# 3_MCU.net
KiCad netlist of a schematic drawn in Altium Designer
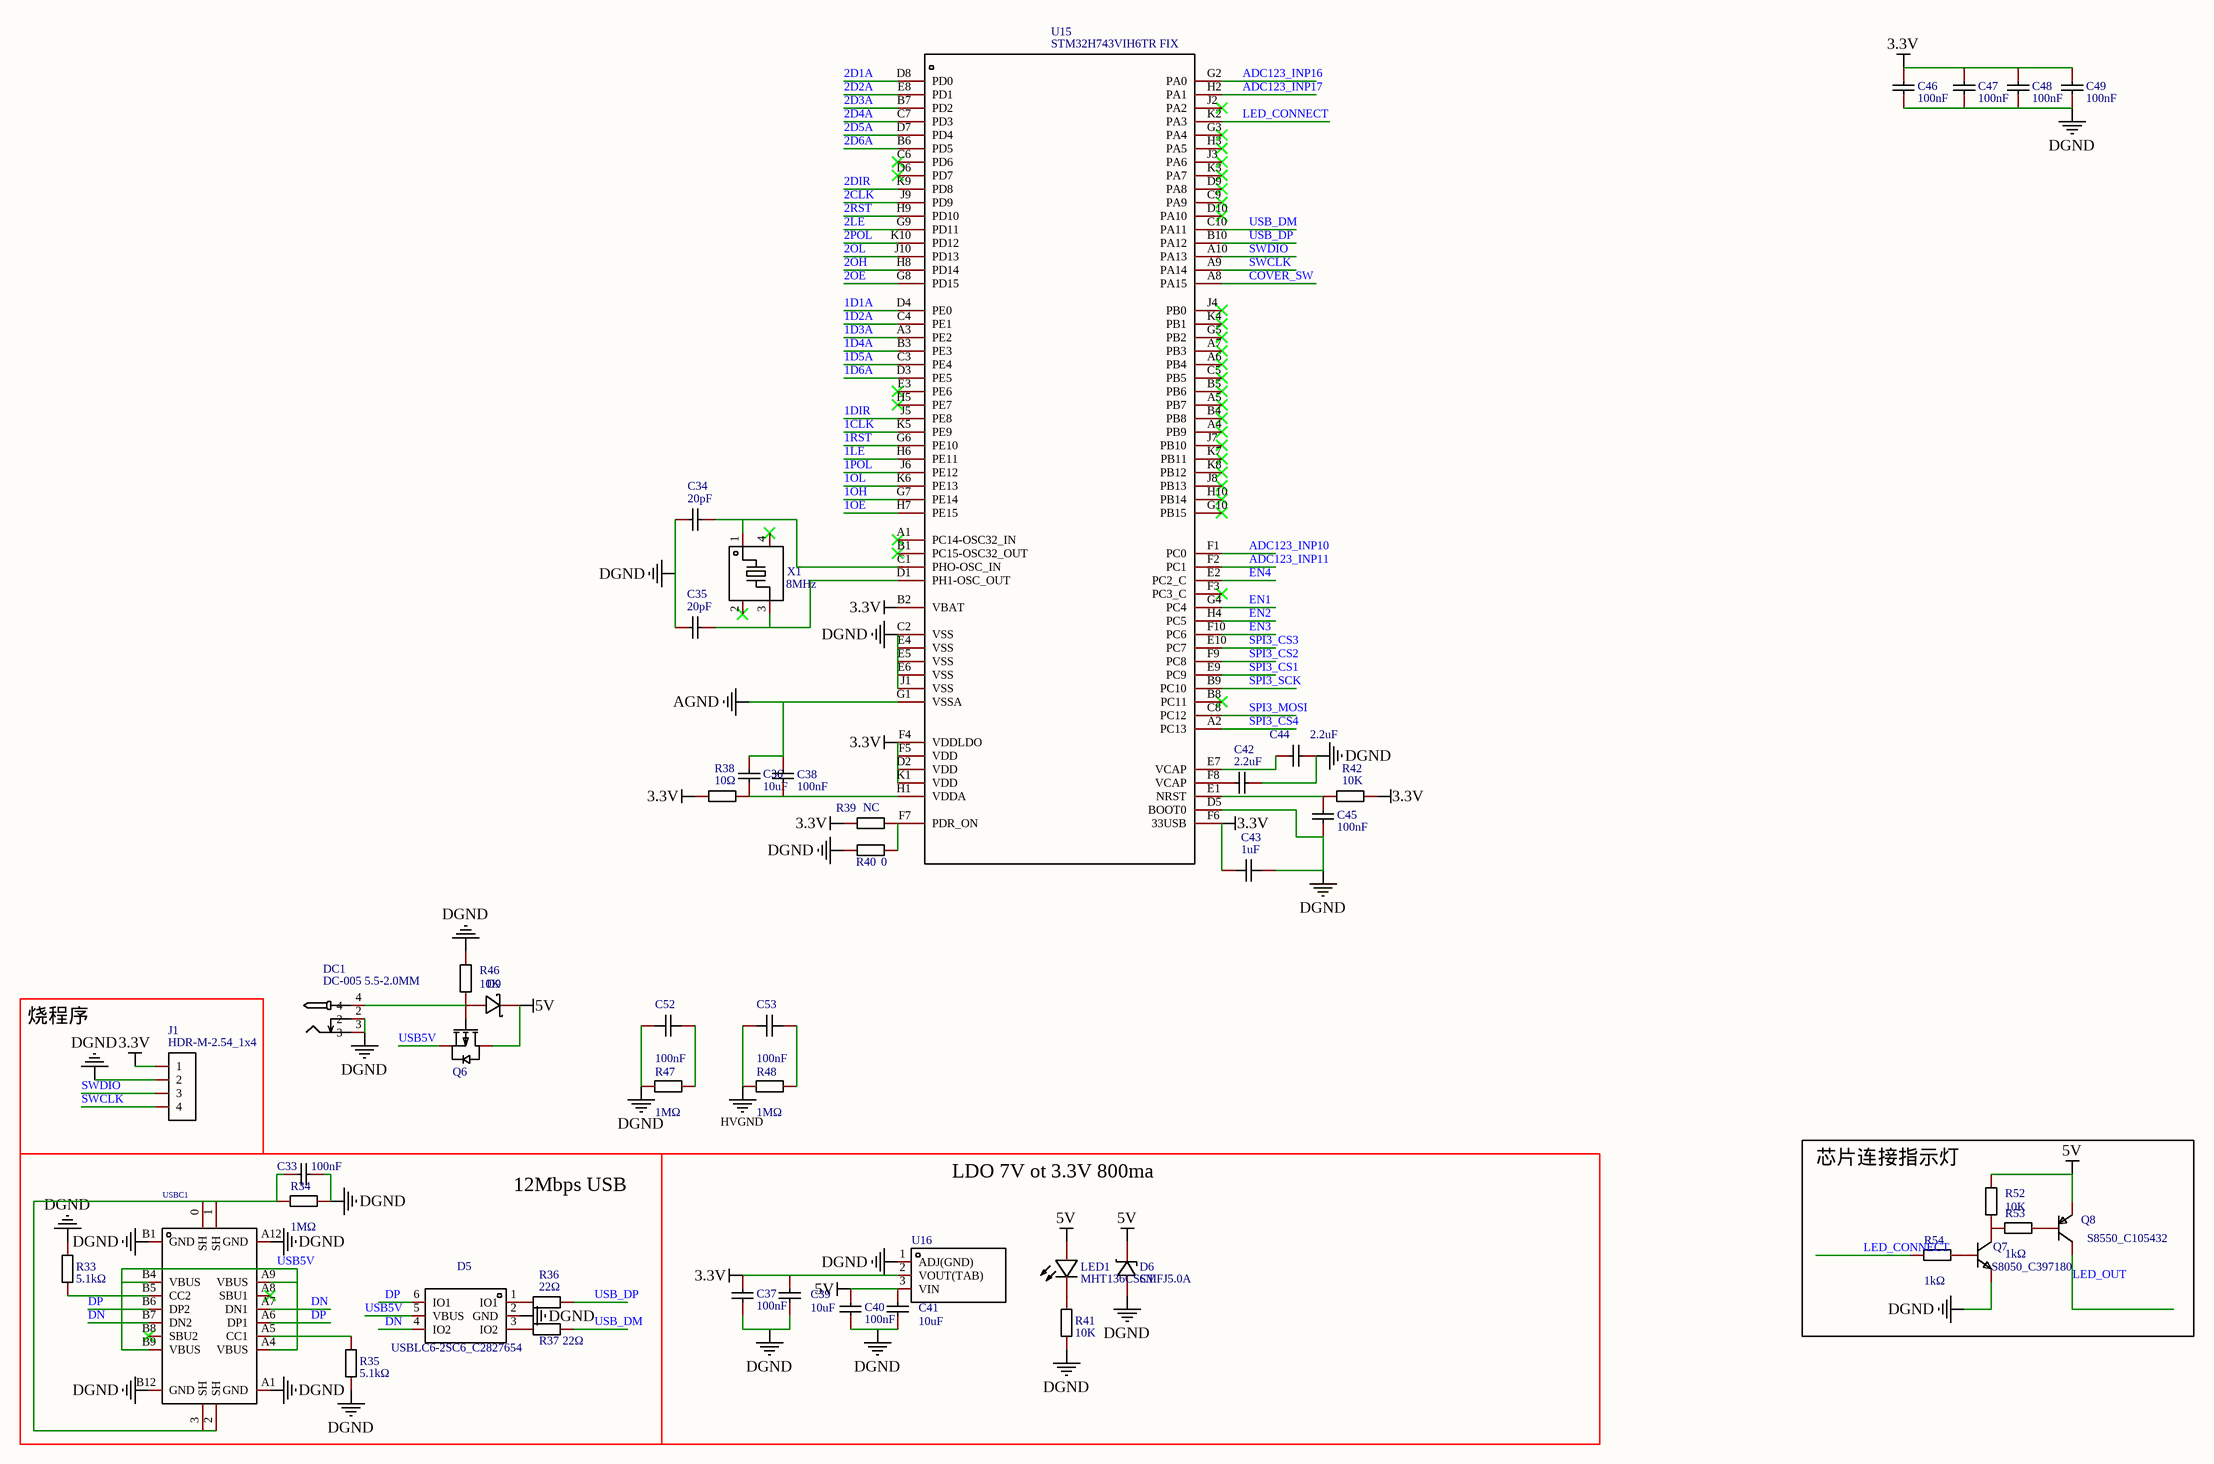
[diagram p0: 3_MCU.schdoc]

(export (version "E")
  (design (tool "Eeschema 10.0.6"))
  (components
    (comp (ref "C33")
      (value "100nF")
      (fields
        (field (name "NAME") "100nF")
        (field (name "MANUFACTURER PART") "CL05B104KO5NNNC")
        (field (name "MANUFACTURER") "SAMSUNG")
      )
      (libsource (lib "altium-import") (part "root_2_CL05B104KO5NNNC_"))
    )
    (comp (ref "C34")
      (value "20pF")
      (fields
        (field (name "NAME") "20pF")
        (field (name "MANUFACTURER") "FH")
        (field (name "MANUFACTURER PART") "0402CG200J500NT")
      )
      (libsource (lib "altium-import") (part "root_2_0402CG200J500NT_"))
    )
    (comp (ref "C35")
      (value "20pF")
      (fields
        (field (name "NAME") "20pF")
        (field (name "MANUFACTURER") "FH")
        (field (name "MANUFACTURER PART") "0402CG200J500NT")
      )
      (libsource (lib "altium-import") (part "root_2_0402CG200J500NT_"))
    )
    (comp (ref "C36")
      (value "10uF")
      (fields
        (field (name "NAME") "10uF")
        (field (name "MANUFACTURER PART") "CL05A106MQ5NUNC")
        (field (name "MANUFACTURER") "SAMSUNG")
      )
      (libsource (lib "altium-import") (part "root_1_CL05A106MQ5NUNC_"))
    )
    (comp (ref "C37")
      (value "100nF")
      (fields
        (field (name "NAME") "100nF")
        (field (name "MANUFACTURER PART") "CL05B104KO5NNNC")
        (field (name "MANUFACTURER") "SAMSUNG")
      )
      (libsource (lib "altium-import") (part "root_1_CL05B104KO5NNNC_"))
    )
    (comp (ref "C38")
      (value "100nF")
      (fields
        (field (name "NAME") "100nF")
        (field (name "MANUFACTURER PART") "CL05B104KO5NNNC")
        (field (name "MANUFACTURER") "SAMSUNG")
      )
      (libsource (lib "altium-import") (part "root_1_CL05B104KO5NNNC_"))
    )
    (comp (ref "C39")
      (value "10uF")
      (description "容值:10uF;精度:±20%;额定电压:6.3V;材质(温度系数):X5R;")
      (fields
        (field (name "MANUFACTURER") "SAMSUNG(三星)")
        (field (name "MANUFACTURER PART") "CL05A106MQ5NUNC")
      )
      (libsource (lib "altium-import") (part "root_1_CL05A106MQ5NUNC_"))
    )
    (comp (ref "C40")
      (value "100nF")
      (fields
        (field (name "NAME") "100nF")
        (field (name "MANUFACTURER PART") "CL05B104KO5NNNC")
        (field (name "MANUFACTURER") "SAMSUNG")
      )
      (libsource (lib "altium-import") (part "root_1_CL05B104KO5NNNC_"))
    )
    (comp (ref "C41")
      (value "10uF")
      (description "容值:10uF;精度:±20%;额定电压:6.3V;材质(温度系数):X5R;")
      (fields
        (field (name "MANUFACTURER") "SAMSUNG(三星)")
        (field (name "MANUFACTURER PART") "CL05A106MQ5NUNC")
      )
      (libsource (lib "altium-import") (part "root_1_CL05A106MQ5NUNC_"))
    )
    (comp (ref "C42")
      (value "2.2uF")
      (fields
        (field (name "NAME") "2.2uF")
        (field (name "MANUFACTURER PART") "GRM155R61A225KE95D")
        (field (name "MANUFACTURER") "MuRata")
      )
      (libsource (lib "altium-import") (part "root_0_GRM155R61A225KE95D_"))
    )
    (comp (ref "C43")
      (value "1uF")
      (fields
        (field (name "NAME") "1uF")
        (field (name "MANUFACTURER") "SAMSUNG")
        (field (name "MANUFACTURER PART") "CL05A105KA5NQNC")
      )
      (libsource (lib "altium-import") (part "root_2_CL05A105KA5NQNC_"))
    )
    (comp (ref "C44")
      (value "2.2uF")
      (fields
        (field (name "NAME") "2.2uF")
        (field (name "MANUFACTURER PART") "GRM155R61A225KE95D")
        (field (name "MANUFACTURER") "MuRata")
      )
      (libsource (lib "altium-import") (part "root_0_GRM155R61A225KE95D_"))
    )
    (comp (ref "C45")
      (value "100nF")
      (fields
        (field (name "NAME") "100nF")
        (field (name "MANUFACTURER PART") "CL05B104KO5NNNC")
        (field (name "MANUFACTURER") "SAMSUNG")
      )
      (libsource (lib "altium-import") (part "root_1_CL05B104KO5NNNC_"))
    )
    (comp (ref "C46")
      (value "100nF")
      (fields
        (field (name "NAME") "100nF")
        (field (name "MANUFACTURER PART") "CL05B104KO5NNNC")
        (field (name "MANUFACTURER") "SAMSUNG")
      )
      (libsource (lib "altium-import") (part "root_1_CL05B104KO5NNNC_"))
    )
    (comp (ref "C47")
      (value "100nF")
      (fields
        (field (name "NAME") "100nF")
        (field (name "MANUFACTURER PART") "CL05B104KO5NNNC")
        (field (name "MANUFACTURER") "SAMSUNG")
      )
      (libsource (lib "altium-import") (part "root_1_CL05B104KO5NNNC_"))
    )
    (comp (ref "C48")
      (value "100nF")
      (fields
        (field (name "NAME") "100nF")
        (field (name "MANUFACTURER PART") "CL05B104KO5NNNC")
        (field (name "MANUFACTURER") "SAMSUNG")
      )
      (libsource (lib "altium-import") (part "root_1_CL05B104KO5NNNC_"))
    )
    (comp (ref "C49")
      (value "100nF")
      (fields
        (field (name "NAME") "100nF")
        (field (name "MANUFACTURER PART") "CL05B104KO5NNNC")
        (field (name "MANUFACTURER") "SAMSUNG")
      )
      (libsource (lib "altium-import") (part "root_1_CL05B104KO5NNNC_"))
    )
    (comp (ref "C52")
      (value "100nF")
      (description "容值:100nF;精度:±10%;额定电压:50V;材质(温度系数):X7R;")
      (fields
        (field (name "MANUFACTURER") "YAGEO(国巨)")
        (field (name "MANUFACTURER PART") "CC0603KRX7R9BB104")
      )
      (libsource (lib "altium-import") (part "root_0_CC0603KRX7R9BB104_"))
    )
    (comp (ref "C53")
      (value "100nF")
      (description "容值:100nF;精度:±10%;额定电压:50V;材质(温度系数):X7R;")
      (fields
        (field (name "MANUFACTURER") "YAGEO(国巨)")
        (field (name "MANUFACTURER PART") "CC0603KRX7R9BB104")
      )
      (libsource (lib "altium-import") (part "root_0_CC0603KRX7R9BB104_"))
    )
    (comp (ref "D5")
      (value "USBLC6-2SC6_C2827654")
      (fields
        (field (name "NAME") "USBLC6-2SC6_C2827654")
        (field (name "MANUFACTURER") "TECH PUBLIC(台舟电子)")
        (field (name "MANUFACTURER PART") "USBLC6-2SC6")
      )
      (libsource (lib "altium-import") (part "root_2_USBLC6-2SC6_"))
    )
    (comp (ref "D6")
      (value "SMFJ5.0A")
      (fields (field (name "NAME") "SMFJ5.0A") (field (name "MANUFACTURER") "RUILON"))
      (libsource (lib "altium-import") (part "root_3_SMFJ5.0A_"))
    )
    (comp (ref "D9")
      (value "SS34_C8678")
      (description "二极管配置:独立式;直流反向耐压(Vr):40V;平均整流电流(Io):3A;正向压降(Vf):550mV@3A;")
      (fields (field (name "MANUFACTURER") "MDD") (field (name "MANUFACTURER PART") "SS34"))
      (libsource (lib "altium-import") (part "root_2_SS34_C8678_"))
    )
    (comp (ref "DC1")
      (value "DC-005 5.5-2.0MM")
      (fields (field (name "NAME") "DC-005 5.5-2.0MM") (field (name "MANUFACTURER") "BOOMELE"))
      (libsource (lib "altium-import") (part "root_0_DC-005 5.5-2.0MM_"))
    )
    (comp (ref "J1")
      (value "HDR-M-2.54_1x4")
      (fields (field (name "NAME") "HDR-M-2.54_1x4"))
      (libsource (lib "altium-import") (part "root_0_HDR-M-2.54_1x4_"))
    )
    (comp (ref "LED1")
      (value "MHT136CSCT")
      (fields (field (name "NAME") "MHT136CSCT") (field (name "MANUFACTURER") "MEIHUA"))
      (libsource (lib "altium-import") (part "root_1_MHT136CSCT_"))
    )
    (comp (ref "Q6")
      (value "CJ3401")
      (description "类型:P沟道;漏源电压(Vdss):30V;连续漏极电流(Id):4.2A;功率(Pd):350mW;导通电阻(RDS(on)@Vgs,Id):65mΩ@10V,4.2A;")
      (fields (field (name "MANUFACTURER") "CJ(江苏长电/长晶)"))
      (libsource (lib "altium-import") (part "root_3_CJ3401_"))
    )
    (comp (ref "Q7")
      (value "S8050_C397180")
      (fields
        (field (name "NAME") "S8050_C397180")
        (field (name "MANUFACTURER") "AnBon")
        (field (name "MANUFACTURER PART") "S8050")
      )
      (libsource (lib "altium-import") (part "root_0_S8050_C397180_"))
    )
    (comp (ref "Q8")
      (value "S8550_C105432")
      (fields
        (field (name "NAME") "S8550_C105432")
        (field (name "MANUFACTURER") "CJ")
        (field (name "MANUFACTURER PART") "S8550")
      )
      (libsource (lib "altium-import") (part "root_2_S8550_C105432_"))
    )
    (comp (ref "R33")
      (value "5.1kΩ")
      (fields
        (field (name "NAME") "5.1kΩ")
        (field (name "MANUFACTURER") "UniOhm")
        (field (name "MANUFACTURER PART") "0402WGF5101TCE")
      )
      (libsource (lib "altium-import") (part "root_1_0402WGF5101TCE_"))
    )
    (comp (ref "R34")
      (value "1MΩ")
      (description "电阻类型:厚膜电阻;阻值:1MΩ;精度:±1%;功率:62.5mW;")
      (fields
        (field (name "MANUFACTURER") "UNI-ROYAL(厚声)")
        (field (name "MANUFACTURER PART") "0402WGF1004TCE")
      )
      (libsource (lib "altium-import") (part "root_0_0402WGF1004TCE_"))
    )
    (comp (ref "R35")
      (value "5.1kΩ")
      (fields
        (field (name "NAME") "5.1kΩ")
        (field (name "MANUFACTURER") "UniOhm")
        (field (name "MANUFACTURER PART") "0402WGF5101TCE")
      )
      (libsource (lib "altium-import") (part "root_1_0402WGF5101TCE_"))
    )
    (comp (ref "R36")
      (value "22Ω")
      (fields
        (field (name "NAME") "22Ω")
        (field (name "MANUFACTURER") "UniOhm")
        (field (name "MANUFACTURER PART") "0402WGF220JTCE")
      )
      (libsource (lib "altium-import") (part "root_0_0402WGF220JTCE_"))
    )
    (comp (ref "R37")
      (value "22Ω")
      (fields
        (field (name "NAME") "22Ω")
        (field (name "MANUFACTURER") "UniOhm")
        (field (name "MANUFACTURER PART") "0402WGF220JTCE")
      )
      (libsource (lib "altium-import") (part "root_0_0402WGF220JTCE_"))
    )
    (comp (ref "R38")
      (value "10Ω")
      (fields
        (field (name "NAME") "10Ω")
        (field (name "MANUFACTURER") "UniOhm")
        (field (name "MANUFACTURER PART") "0402WGF100JTCE")
      )
      (libsource (lib "altium-import") (part "root_0_0402WGF100JTCE_"))
    )
    (comp (ref "R39")
      (value "NC")
      (fields (field (name "NAME") "NC") (field (name "MANUFACTURER") "UniOhm"))
      (libsource (lib "altium-import") (part "root_0_NC_"))
    )
    (comp (ref "R40")
      (value "0")
      (fields
        (field (name "NAME") "0")
        (field (name "MANUFACTURER") "UniOhm")
        (field (name "MANUFACTURER PART") "0402WGF100JTCE")
      )
      (libsource (lib "altium-import") (part "root_0_0402WGF100JTCE_"))
    )
    (comp (ref "R41")
      (value "10K")
      (fields
        (field (name "NAME") "10K")
        (field (name "MANUFACTURER") "UniOhm")
        (field (name "MANUFACTURER PART") "0402WGF1002TCE")
      )
      (libsource (lib "altium-import") (part "root_1_0402WGF1002TCE_"))
    )
    (comp (ref "R42")
      (value "10K")
      (fields
        (field (name "NAME") "10K")
        (field (name "MANUFACTURER") "UniOhm")
        (field (name "MANUFACTURER PART") "0402WGF1002TCE")
      )
      (libsource (lib "altium-import") (part "root_0_0402WGF1002TCE_"))
    )
    (comp (ref "R46")
      (value "10K")
      (fields
        (field (name "NAME") "10K")
        (field (name "MANUFACTURER") "UniOhm")
        (field (name "MANUFACTURER PART") "0402WGF1002TCE")
      )
      (libsource (lib "altium-import") (part "root_1_0402WGF1002TCE_"))
    )
    (comp (ref "R47")
      (value "1MΩ")
      (description "电阻类型:厚膜电阻;阻值:1MΩ;精度:±1%;功率:100mW;")
      (fields
        (field (name "MANUFACTURER") "UNI-ROYAL(厚声)")
        (field (name "MANUFACTURER PART") "0603WAF1004T5E")
      )
      (libsource (lib "altium-import") (part "root_0_0603WAF1004T5E_"))
    )
    (comp (ref "R48")
      (value "1MΩ")
      (description "电阻类型:厚膜电阻;阻值:1MΩ;精度:±1%;功率:100mW;")
      (fields
        (field (name "MANUFACTURER") "UNI-ROYAL(厚声)")
        (field (name "MANUFACTURER PART") "0603WAF1004T5E")
      )
      (libsource (lib "altium-import") (part "root_0_0603WAF1004T5E_"))
    )
    (comp (ref "R52")
      (value "10K")
      (fields
        (field (name "NAME") "10K")
        (field (name "MANUFACTURER") "UniOhm")
        (field (name "MANUFACTURER PART") "0402WGF1002TCE")
      )
      (libsource (lib "altium-import") (part "root_1_0402WGF1002TCE_"))
    )
    (comp (ref "R53")
      (value "1kΩ")
      (description "电阻类型:厚膜电阻;阻值:1kΩ;精度:±1%;功率:62.5mW;")
      (fields
        (field (name "MANUFACTURER") "UNI-ROYAL(厚声)")
        (field (name "MANUFACTURER PART") "0402WGF1001TCE")
      )
      (libsource (lib "altium-import") (part "root_0_0402WGF1001TCE_"))
    )
    (comp (ref "R54")
      (value "1kΩ")
      (description "电阻类型:厚膜电阻;阻值:1kΩ;精度:±1%;功率:62.5mW;")
      (fields
        (field (name "MANUFACTURER") "UNI-ROYAL(厚声)")
        (field (name "MANUFACTURER PART") "0402WGF1001TCE")
      )
      (libsource (lib "altium-import") (part "root_0_0402WGF1001TCE_"))
    )
    (comp (ref "U15")
      (value "STM32H743VIH6TR FIX")
      (fields
        (field (name "NAME") "STM32H743VIH6TR FIX")
        (field (name "MANUFACTURER") "ST(意法半导体)")
        (field (name "MANUFACTURER PART") "STM32H743VIH6TR")
      )
      (libsource (lib "altium-import") (part "root_0_STM32H743VIH6TR_"))
    )
    (comp (ref "U16")
      (value "AMS1117-3.3_C347256")
      (description "输出类型:固定;输出极性:正;最大输入电压:18V;输出电压:3.3V;输出电流:1A;电源纹波抑制比(PSRR):60dB@(120Hz);")
      (fields (field (name "MANUFACTURER") "UMW(广东友台半导体)") (field (name "MANUFACTURER PART") "AMS1117-3.3"))
      (libsource (lib "altium-import") (part "root_0_AMS1117-3.3_C347256_"))
    )
    (comp (ref "USBC1")
      (value "TYPE-C-31-M-12")
      (description "连接器类型:Type-C;标准:-;公母:母座;触点数量:16P;端口数量:1;安装方式:-;额定电流 - 电源:5A;触头材质:-;触头镀层:-;工作温度范围:-;焊接温度(最大值):-;")
      (fields (field (name "MANUFACTURER") "韩国韩荣"))
      (libsource (lib "altium-import") (part "root_0_TYPE-C-31-M-12_"))
    )
    (comp (ref "X1")
      (value "8MHz")
      (fields
        (field (name "NAME") "8MHz")
        (field (name "MANUFACTURER") "Suzhou Liming Elec")
        (field (name "MANUFACTURER PART") "3225-8.00-20-10-10/A")
      )
      (libsource (lib "altium-import") (part "root_3_3225-8.00-20-10-10/A_"))
    )
  )
  (nets
    (net (code "1") (name "/1CLK") (class "Default")
      (node (ref "U15") (pin "K5") (pinfunction "PE9_K5") (pintype "passive"))
    )
    (net (code "2") (name "/1D1A") (class "Default")
      (node (ref "U15") (pin "D4") (pinfunction "PE0_D4") (pintype "passive"))
    )
    (net (code "3") (name "/1D2A") (class "Default")
      (node (ref "U15") (pin "C4") (pinfunction "PE1_C4") (pintype "passive"))
    )
    (net (code "4") (name "/1D3A") (class "Default")
      (node (ref "U15") (pin "A3") (pinfunction "PE2_A3") (pintype "passive"))
    )
    (net (code "5") (name "/1D4A") (class "Default")
      (node (ref "U15") (pin "B3") (pinfunction "PE3_B3") (pintype "passive"))
    )
    (net (code "6") (name "/1D5A") (class "Default")
      (node (ref "U15") (pin "C3") (pinfunction "PE4_C3") (pintype "passive"))
    )
    (net (code "7") (name "/1D6A") (class "Default")
      (node (ref "U15") (pin "D3") (pinfunction "PE5_D3") (pintype "passive"))
    )
    (net (code "8") (name "/1DIR") (class "Default")
      (node (ref "U15") (pin "J5") (pinfunction "PE8_J5") (pintype "passive"))
    )
    (net (code "9") (name "/1LE") (class "Default")
      (node (ref "U15") (pin "H6") (pinfunction "PE11_H6") (pintype "passive"))
    )
    (net (code "10") (name "/1OE") (class "Default")
      (node (ref "U15") (pin "H7") (pinfunction "PE15_H7") (pintype "passive"))
    )
    (net (code "11") (name "/1OH") (class "Default")
      (node (ref "U15") (pin "G7") (pinfunction "PE14_G7") (pintype "passive"))
    )
    (net (code "12") (name "/1OL") (class "Default")
      (node (ref "U15") (pin "K6") (pinfunction "PE13_K6") (pintype "passive"))
    )
    (net (code "13") (name "/1POL") (class "Default")
      (node (ref "U15") (pin "J6") (pinfunction "PE12_J6") (pintype "passive"))
    )
    (net (code "14") (name "/1RST") (class "Default")
      (node (ref "U15") (pin "G6") (pinfunction "PE10_G6") (pintype "passive"))
    )
    (net (code "15") (name "/2CLK") (class "Default")
      (node (ref "U15") (pin "J9") (pinfunction "PD9_J9") (pintype "passive"))
    )
    (net (code "16") (name "/2D1A") (class "Default")
      (node (ref "U15") (pin "D8") (pinfunction "PD0_D8") (pintype "passive"))
    )
    (net (code "17") (name "/2D2A") (class "Default")
      (node (ref "U15") (pin "E8") (pinfunction "PD1_E8") (pintype "passive"))
    )
    (net (code "18") (name "/2D3A") (class "Default")
      (node (ref "U15") (pin "B7") (pinfunction "PD2_B7") (pintype "passive"))
    )
    (net (code "19") (name "/2D4A") (class "Default")
      (node (ref "U15") (pin "C7") (pinfunction "PD3_C7") (pintype "passive"))
    )
    (net (code "20") (name "/2D5A") (class "Default")
      (node (ref "U15") (pin "D7") (pinfunction "PD4_D7") (pintype "passive"))
    )
    (net (code "21") (name "/2D6A") (class "Default")
      (node (ref "U15") (pin "B6") (pinfunction "PD5_B6") (pintype "passive"))
    )
    (net (code "22") (name "/2DIR") (class "Default")
      (node (ref "U15") (pin "K9") (pinfunction "PD8_K9") (pintype "passive"))
    )
    (net (code "23") (name "/2LE") (class "Default")
      (node (ref "U15") (pin "G9") (pinfunction "PD11_G9") (pintype "passive"))
    )
    (net (code "24") (name "/2OE") (class "Default")
      (node (ref "U15") (pin "G8") (pinfunction "PD15_G8") (pintype "passive"))
    )
    (net (code "25") (name "/2OH") (class "Default")
      (node (ref "U15") (pin "H8") (pinfunction "PD14_H8") (pintype "passive"))
    )
    (net (code "26") (name "/2OL") (class "Default")
      (node (ref "U15") (pin "J10") (pinfunction "PD13_J10") (pintype "passive"))
    )
    (net (code "27") (name "/2POL") (class "Default")
      (node (ref "U15") (pin "K10") (pinfunction "PD12_K10") (pintype "passive"))
    )
    (net (code "28") (name "/2RST") (class "Default")
      (node (ref "U15") (pin "H9") (pinfunction "PD10_H9") (pintype "passive"))
    )
    (net (code "29") (name "/ADC123_INP10") (class "Default")
      (node (ref "U15") (pin "F1") (pinfunction "PC0_F1") (pintype "passive"))
    )
    (net (code "30") (name "/ADC123_INP11") (class "Default")
      (node (ref "U15") (pin "F2") (pinfunction "PC1_F2") (pintype "passive"))
    )
    (net (code "31") (name "/ADC123_INP16") (class "Default")
      (node (ref "U15") (pin "G2") (pinfunction "PA0_G2") (pintype "passive"))
    )
    (net (code "32") (name "/ADC123_INP17") (class "Default")
      (node (ref "U15") (pin "H2") (pinfunction "PA1_H2") (pintype "passive"))
    )
    (net (code "33") (name "/COVER_SW") (class "Default")
      (node (ref "U15") (pin "A8") (pinfunction "PA15_A8") (pintype "passive"))
    )
    (net (code "34") (name "/DN") (class "Default")
      (node (ref "D5") (pin "4") (pinfunction "IO2_4") (pintype "passive"))
      (node (ref "USBC1") (pin "A7") (pinfunction "DN1_A7") (pintype "passive"))
      (node (ref "USBC1") (pin "B7") (pinfunction "DN2_B7") (pintype "passive"))
    )
    (net (code "35") (name "/DP") (class "Default")
      (node (ref "D5") (pin "6") (pinfunction "IO1_6") (pintype "passive"))
      (node (ref "USBC1") (pin "A6") (pinfunction "DP1_A6") (pintype "passive"))
      (node (ref "USBC1") (pin "B6") (pinfunction "DP2_B6") (pintype "passive"))
    )
    (net (code "36") (name "/EN1") (class "Default")
      (node (ref "U15") (pin "G4") (pinfunction "PC4_G4") (pintype "passive"))
    )
    (net (code "37") (name "/EN2") (class "Default")
      (node (ref "U15") (pin "H4") (pinfunction "PC5_H4") (pintype "passive"))
    )
    (net (code "38") (name "/EN3") (class "Default")
      (node (ref "U15") (pin "F10") (pinfunction "PC6_F10") (pintype "passive"))
    )
    (net (code "39") (name "/EN4") (class "Default")
      (node (ref "U15") (pin "E2") (pinfunction "PC2_C_E2") (pintype "passive"))
    )
    (net (code "40") (name "/LED_CONNECT") (class "Default")
      (node (ref "R54") (pin "1") (pinfunction "1_1") (pintype "passive"))
      (node (ref "U15") (pin "K2") (pinfunction "PA3_K2") (pintype "passive"))
    )
    (net (code "41") (name "/LED_OUT") (class "Default")
      (node (ref "Q8") (pin "3") (pinfunction "3_3") (pintype "passive"))
    )
    (net (code "42") (name "/SPI3_CS1") (class "Default")
      (node (ref "U15") (pin "E9") (pinfunction "PC9_E9") (pintype "passive"))
    )
    (net (code "43") (name "/SPI3_CS2") (class "Default")
      (node (ref "U15") (pin "F9") (pinfunction "PC8_F9") (pintype "passive"))
    )
    (net (code "44") (name "/SPI3_CS3") (class "Default")
      (node (ref "U15") (pin "E10") (pinfunction "PC7_E10") (pintype "passive"))
    )
    (net (code "45") (name "/SPI3_CS4") (class "Default")
      (node (ref "U15") (pin "A2") (pinfunction "PC13_A2") (pintype "passive"))
    )
    (net (code "46") (name "/SPI3_MOSI") (class "Default")
      (node (ref "U15") (pin "C8") (pinfunction "PC12_C8") (pintype "passive"))
    )
    (net (code "47") (name "/SPI3_SCK") (class "Default")
      (node (ref "U15") (pin "B9") (pinfunction "PC10_B9") (pintype "passive"))
    )
    (net (code "48") (name "/SWCLK") (class "Default")
      (node (ref "J1") (pin "4") (pinfunction "4_4") (pintype "passive"))
      (node (ref "U15") (pin "A9") (pinfunction "PA14_A9") (pintype "passive"))
    )
    (net (code "49") (name "/SWDIO") (class "Default")
      (node (ref "J1") (pin "3") (pinfunction "3_3") (pintype "passive"))
      (node (ref "U15") (pin "A10") (pinfunction "PA13_A10") (pintype "passive"))
    )
    (net (code "50") (name "/USB5V") (class "Default")
      (node (ref "D5") (pin "5") (pinfunction "VBUS_5") (pintype "passive"))
      (node (ref "Q6") (pin "2") (pinfunction "S_2") (pintype "passive"))
      (node (ref "USBC1") (pin "A4") (pinfunction "VBUS_A4") (pintype "passive"))
      (node (ref "USBC1") (pin "A9") (pinfunction "VBUS_A9") (pintype "passive"))
      (node (ref "USBC1") (pin "B4") (pinfunction "VBUS_B4") (pintype "passive"))
      (node (ref "USBC1") (pin "B9") (pinfunction "VBUS_B9") (pintype "passive"))
    )
    (net (code "51") (name "/USB_DM") (class "Default")
      (node (ref "R37") (pin "2") (pinfunction "2_2") (pintype "passive"))
      (node (ref "U15") (pin "C10") (pinfunction "PA11_C10") (pintype "passive"))
    )
    (net (code "52") (name "/USB_DP") (class "Default")
      (node (ref "R36") (pin "2") (pinfunction "2_2") (pintype "passive"))
      (node (ref "U15") (pin "B10") (pinfunction "PA12_B10") (pintype "passive"))
    )
    (net (code "53") (name "3.3V") (class "Default")
      (node (ref "C37") (pin "2") (pinfunction "2_2") (pintype "passive"))
      (node (ref "C39") (pin "2") (pinfunction "2_2") (pintype "passive"))
      (node (ref "C43") (pin "2") (pinfunction "2_2") (pintype "passive"))
      (node (ref "C46") (pin "2") (pinfunction "2_2") (pintype "passive"))
      (node (ref "C47") (pin "2") (pinfunction "2_2") (pintype "passive"))
      (node (ref "C48") (pin "2") (pinfunction "2_2") (pintype "passive"))
      (node (ref "C49") (pin "2") (pinfunction "2_2") (pintype "passive"))
      (node (ref "J1") (pin "1") (pinfunction "1_1") (pintype "passive"))
      (node (ref "R38") (pin "1") (pinfunction "1_1") (pintype "passive"))
      (node (ref "R39") (pin "1") (pinfunction "1_1") (pintype "passive"))
      (node (ref "R42") (pin "2") (pinfunction "2_2") (pintype "passive"))
      (node (ref "U15") (pin "B2") (pinfunction "VBAT_B2") (pintype "passive"))
      (node (ref "U15") (pin "D2") (pinfunction "VDD_D2") (pintype "passive"))
      (node (ref "U15") (pin "F4") (pinfunction "VDDLDO_F4") (pintype "passive"))
      (node (ref "U15") (pin "F5") (pinfunction "VDD_F5") (pintype "passive"))
      (node (ref "U15") (pin "F6") (pinfunction "33USB_F6") (pintype "passive"))
      (node (ref "U15") (pin "K1") (pinfunction "VDD_K1") (pintype "passive"))
      (node (ref "U16") (pin "2") (pinfunction "VOUT(TAB)_2") (pintype "passive"))
    )
    (net (code "54") (name "5V") (class "Default")
      (node (ref "C40") (pin "2") (pinfunction "2_2") (pintype "passive"))
      (node (ref "C41") (pin "2") (pinfunction "2_2") (pintype "passive"))
      (node (ref "D6") (pin "1") (pinfunction "K_1") (pintype "passive"))
      (node (ref "D9") (pin "1") (pinfunction "K_1") (pintype "passive"))
      (node (ref "LED1") (pin "2") (pinfunction "A_2") (pintype "passive"))
      (node (ref "Q6") (pin "3") (pinfunction "D_3") (pintype "passive"))
      (node (ref "Q8") (pin "2") (pinfunction "2_2") (pintype "passive"))
      (node (ref "R52") (pin "2") (pinfunction "2_2") (pintype "passive"))
      (node (ref "U16") (pin "3") (pinfunction "VIN_3") (pintype "passive"))
    )
    (net (code "55") (name "AGND") (class "Default")
      (node (ref "C36") (pin "2") (pinfunction "2_2") (pintype "passive"))
      (node (ref "C38") (pin "2") (pinfunction "2_2") (pintype "passive"))
      (node (ref "U15") (pin "G1") (pinfunction "VSSA_G1") (pintype "passive"))
    )
    (net (code "56") (name "DGND") (class "Default")
      (node (ref "C33") (pin "1") (pinfunction "1_1") (pintype "passive"))
      (node (ref "C34") (pin "2") (pinfunction "2_2") (pintype "passive"))
      (node (ref "C35") (pin "2") (pinfunction "2_2") (pintype "passive"))
      (node (ref "C37") (pin "1") (pinfunction "1_1") (pintype "passive"))
      (node (ref "C39") (pin "1") (pinfunction "1_1") (pintype "passive"))
      (node (ref "C40") (pin "1") (pinfunction "1_1") (pintype "passive"))
      (node (ref "C41") (pin "1") (pinfunction "1_1") (pintype "passive"))
      (node (ref "C42") (pin "2") (pinfunction "2_2") (pintype "passive"))
      (node (ref "C43") (pin "1") (pinfunction "1_1") (pintype "passive"))
      (node (ref "C44") (pin "2") (pinfunction "2_2") (pintype "passive"))
      (node (ref "C45") (pin "1") (pinfunction "1_1") (pintype "passive"))
      (node (ref "C46") (pin "1") (pinfunction "1_1") (pintype "passive"))
      (node (ref "C47") (pin "1") (pinfunction "1_1") (pintype "passive"))
      (node (ref "C48") (pin "1") (pinfunction "1_1") (pintype "passive"))
      (node (ref "C49") (pin "1") (pinfunction "1_1") (pintype "passive"))
      (node (ref "C52") (pin "1") (pinfunction "1_1") (pintype "passive"))
      (node (ref "D5") (pin "2") (pinfunction "GND_2") (pintype "passive"))
      (node (ref "D6") (pin "2") (pinfunction "A_2") (pintype "passive"))
      (node (ref "DC1") (pin "2") (pinfunction "2_2") (pintype "passive"))
      (node (ref "DC1") (pin "3") (pinfunction "3_3") (pintype "passive"))
      (node (ref "J1") (pin "2") (pinfunction "2_2") (pintype "passive"))
      (node (ref "Q7") (pin "2") (pinfunction "E_2") (pintype "passive"))
      (node (ref "R33") (pin "2") (pinfunction "2_2") (pintype "passive"))
      (node (ref "R34") (pin "2") (pinfunction "2_2") (pintype "passive"))
      (node (ref "R35") (pin "1") (pinfunction "1_1") (pintype "passive"))
      (node (ref "R40") (pin "1") (pinfunction "1_1") (pintype "passive"))
      (node (ref "R41") (pin "1") (pinfunction "1_1") (pintype "passive"))
      (node (ref "R46") (pin "2") (pinfunction "2_2") (pintype "passive"))
      (node (ref "R47") (pin "1") (pinfunction "1_1") (pintype "passive"))
      (node (ref "U15") (pin "C2") (pinfunction "VSS_C2") (pintype "passive"))
      (node (ref "U15") (pin "D5") (pinfunction "BOOT0_D5") (pintype "passive"))
      (node (ref "U15") (pin "E4") (pinfunction "VSS_E4") (pintype "passive"))
      (node (ref "U15") (pin "E5") (pinfunction "VSS_E5") (pintype "passive"))
      (node (ref "U15") (pin "E6") (pinfunction "VSS_E6") (pintype "passive"))
      (node (ref "U15") (pin "J1") (pinfunction "VSS_J1") (pintype "passive"))
      (node (ref "U16") (pin "1") (pinfunction "ADJ(GND)_1") (pintype "passive"))
      (node (ref "USBC1") (pin "A1") (pinfunction "GND_A1") (pintype "passive"))
      (node (ref "USBC1") (pin "A12") (pinfunction "GND_A12") (pintype "passive"))
      (node (ref "USBC1") (pin "B1") (pinfunction "GND_B1") (pintype "passive"))
      (node (ref "USBC1") (pin "B12") (pinfunction "GND_B12") (pintype "passive"))
    )
    (net (code "57") (name "HVGND") (class "Default")
      (node (ref "C53") (pin "1") (pinfunction "1_1") (pintype "passive"))
      (node (ref "R48") (pin "1") (pinfunction "1_1") (pintype "passive"))
    )
    (net (code "58") (name "Net-(C33-Pad2)") (class "Default")
      (node (ref "C33") (pin "2") (pinfunction "2_2") (pintype "passive"))
      (node (ref "R34") (pin "1") (pinfunction "1_1") (pintype "passive"))
      (node (ref "USBC1") (pin "0") (pinfunction "SH_0") (pintype "passive"))
      (node (ref "USBC1") (pin "1") (pinfunction "SH_1") (pintype "passive"))
      (node (ref "USBC1") (pin "2") (pinfunction "SH_2") (pintype "passive"))
      (node (ref "USBC1") (pin "3") (pinfunction "SH_3") (pintype "passive"))
    )
    (net (code "59") (name "Net-(C42-Pad1)") (class "Default")
      (node (ref "C42") (pin "1") (pinfunction "1_1") (pintype "passive"))
      (node (ref "U15") (pin "F8") (pinfunction "VCAP_F8") (pintype "passive"))
    )
    (net (code "60") (name "Net-(C44-Pad1)") (class "Default")
      (node (ref "C44") (pin "1") (pinfunction "1_1") (pintype "passive"))
      (node (ref "U15") (pin "E7") (pinfunction "VCAP_E7") (pintype "passive"))
    )
    (net (code "61") (name "Net-(C52-Pad2)") (class "Default")
      (node (ref "C52") (pin "2") (pinfunction "2_2") (pintype "passive"))
      (node (ref "R47") (pin "2") (pinfunction "2_2") (pintype "passive"))
    )
    (net (code "62") (name "Net-(C53-Pad2)") (class "Default")
      (node (ref "C53") (pin "2") (pinfunction "2_2") (pintype "passive"))
      (node (ref "R48") (pin "2") (pinfunction "2_2") (pintype "passive"))
    )
    (net (code "63") (name "Net-(D5-IO1-Pad1)") (class "Default")
      (node (ref "D5") (pin "1") (pinfunction "IO1_1") (pintype "passive"))
      (node (ref "R36") (pin "1") (pinfunction "1_1") (pintype "passive"))
    )
    (net (code "64") (name "Net-(D5-IO2-Pad3)") (class "Default")
      (node (ref "D5") (pin "3") (pinfunction "IO2_3") (pintype "passive"))
      (node (ref "R37") (pin "1") (pinfunction "1_1") (pintype "passive"))
    )
    (net (code "65") (name "Net-(D9-A)") (class "Default")
      (node (ref "D9") (pin "2") (pinfunction "A_2") (pintype "passive"))
      (node (ref "DC1") (pin "4") (pinfunction "4_4") (pintype "passive"))
      (node (ref "Q6") (pin "1") (pinfunction "G_1") (pintype "passive"))
      (node (ref "R46") (pin "1") (pinfunction "1_1") (pintype "passive"))
    )
    (net (code "66") (name "Net-(LED1-K)") (class "Default")
      (node (ref "LED1") (pin "1") (pinfunction "K_1") (pintype "passive"))
      (node (ref "R41") (pin "2") (pinfunction "2_2") (pintype "passive"))
    )
    (net (code "67") (name "Net-(Q7-B)") (class "Default")
      (node (ref "Q7") (pin "1") (pinfunction "B_1") (pintype "passive"))
      (node (ref "R54") (pin "2") (pinfunction "2_2") (pintype "passive"))
    )
    (net (code "68") (name "Net-(Q7-C)") (class "Default")
      (node (ref "Q7") (pin "3") (pinfunction "C_3") (pintype "passive"))
      (node (ref "R52") (pin "1") (pinfunction "1_1") (pintype "passive"))
      (node (ref "R53") (pin "1") (pinfunction "1_1") (pintype "passive"))
    )
    (net (code "69") (name "Net-(Q8-Pad1)") (class "Default")
      (node (ref "Q8") (pin "1") (pinfunction "1_1") (pintype "passive"))
      (node (ref "R53") (pin "2") (pinfunction "2_2") (pintype "passive"))
    )
    (net (code "70") (name "Net-(U15-NRST)") (class "Default")
      (node (ref "C45") (pin "2") (pinfunction "2_2") (pintype "passive"))
      (node (ref "R42") (pin "1") (pinfunction "1_1") (pintype "passive"))
      (node (ref "U15") (pin "E1") (pinfunction "NRST_E1") (pintype "passive"))
    )
    (net (code "71") (name "Net-(U15-PDR_ON)") (class "Default")
      (node (ref "R39") (pin "2") (pinfunction "2_2") (pintype "passive"))
      (node (ref "R40") (pin "2") (pinfunction "2_2") (pintype "passive"))
      (node (ref "U15") (pin "F7") (pinfunction "PDR_ON_F7") (pintype "passive"))
    )
    (net (code "72") (name "Net-(U15-PH1-OSC_OUT)") (class "Default")
      (node (ref "C35") (pin "1") (pinfunction "1_1") (pintype "passive"))
      (node (ref "U15") (pin "D1") (pinfunction "PH1-OSC_OUT_D1") (pintype "passive"))
      (node (ref "X1") (pin "3") (pinfunction "3_3") (pintype "passive"))
    )
    (net (code "73") (name "Net-(U15-PHO-OSC_IN)") (class "Default")
      (node (ref "C34") (pin "1") (pinfunction "1_1") (pintype "passive"))
      (node (ref "U15") (pin "C1") (pinfunction "PHO-OSC_IN_C1") (pintype "passive"))
      (node (ref "X1") (pin "1") (pinfunction "1_1") (pintype "passive"))
    )
    (net (code "74") (name "Net-(U15-VDDA)") (class "Default")
      (node (ref "C36") (pin "1") (pinfunction "1_1") (pintype "passive"))
      (node (ref "C38") (pin "1") (pinfunction "1_1") (pintype "passive"))
      (node (ref "R38") (pin "2") (pinfunction "2_2") (pintype "passive"))
      (node (ref "U15") (pin "H1") (pinfunction "VDDA_H1") (pintype "passive"))
    )
    (net (code "75") (name "Net-(USBC1-CC1)") (class "Default")
      (node (ref "R35") (pin "2") (pinfunction "2_2") (pintype "passive"))
      (node (ref "USBC1") (pin "A5") (pinfunction "CC1_A5") (pintype "passive"))
    )
    (net (code "76") (name "Net-(USBC1-CC2)") (class "Default")
      (node (ref "R33") (pin "1") (pinfunction "1_1") (pintype "passive"))
      (node (ref "USBC1") (pin "B5") (pinfunction "CC2_B5") (pintype "passive"))
    )
    (net (code "77") (name "unconnected-(U15-PA2-PadJ2)") (class "Default")
      (node (ref "U15") (pin "J2") (pinfunction "PA2_J2") (pintype "passive+no_connect"))
    )
    (net (code "78") (name "unconnected-(U15-PA4-PadG3)") (class "Default")
      (node (ref "U15") (pin "G3") (pinfunction "PA4_G3") (pintype "passive+no_connect"))
    )
    (net (code "79") (name "unconnected-(U15-PA5-PadH3)") (class "Default")
      (node (ref "U15") (pin "H3") (pinfunction "PA5_H3") (pintype "passive+no_connect"))
    )
    (net (code "80") (name "unconnected-(U15-PA6-PadJ3)") (class "Default")
      (node (ref "U15") (pin "J3") (pinfunction "PA6_J3") (pintype "passive+no_connect"))
    )
    (net (code "81") (name "unconnected-(U15-PA7-PadK3)") (class "Default")
      (node (ref "U15") (pin "K3") (pinfunction "PA7_K3") (pintype "passive+no_connect"))
    )
    (net (code "82") (name "unconnected-(U15-PA8-PadD9)") (class "Default")
      (node (ref "U15") (pin "D9") (pinfunction "PA8_D9") (pintype "passive+no_connect"))
    )
    (net (code "83") (name "unconnected-(U15-PA9-PadC9)") (class "Default")
      (node (ref "U15") (pin "C9") (pinfunction "PA9_C9") (pintype "passive+no_connect"))
    )
    (net (code "84") (name "unconnected-(U15-PA10-PadD10)") (class "Default")
      (node (ref "U15") (pin "D10") (pinfunction "PA10_D10") (pintype "passive+no_connect"))
    )
    (net (code "85") (name "unconnected-(U15-PB0-PadJ4)") (class "Default")
      (node (ref "U15") (pin "J4") (pinfunction "PB0_J4") (pintype "passive+no_connect"))
    )
    (net (code "86") (name "unconnected-(U15-PB1-PadK4)") (class "Default")
      (node (ref "U15") (pin "K4") (pinfunction "PB1_K4") (pintype "passive+no_connect"))
    )
    (net (code "87") (name "unconnected-(U15-PB2-PadG5)") (class "Default")
      (node (ref "U15") (pin "G5") (pinfunction "PB2_G5") (pintype "passive+no_connect"))
    )
    (net (code "88") (name "unconnected-(U15-PB3-PadA7)") (class "Default")
      (node (ref "U15") (pin "A7") (pinfunction "PB3_A7") (pintype "passive+no_connect"))
    )
    (net (code "89") (name "unconnected-(U15-PB4-PadA6)") (class "Default")
      (node (ref "U15") (pin "A6") (pinfunction "PB4_A6") (pintype "passive+no_connect"))
    )
    (net (code "90") (name "unconnected-(U15-PB5-PadC5)") (class "Default")
      (node (ref "U15") (pin "C5") (pinfunction "PB5_C5") (pintype "passive+no_connect"))
    )
    (net (code "91") (name "unconnected-(U15-PB6-PadB5)") (class "Default")
      (node (ref "U15") (pin "B5") (pinfunction "PB6_B5") (pintype "passive+no_connect"))
    )
    (net (code "92") (name "unconnected-(U15-PB7-PadA5)") (class "Default")
      (node (ref "U15") (pin "A5") (pinfunction "PB7_A5") (pintype "passive+no_connect"))
    )
    (net (code "93") (name "unconnected-(U15-PB8-PadB4)") (class "Default")
      (node (ref "U15") (pin "B4") (pinfunction "PB8_B4") (pintype "passive+no_connect"))
    )
    (net (code "94") (name "unconnected-(U15-PB9-PadA4)") (class "Default")
      (node (ref "U15") (pin "A4") (pinfunction "PB9_A4") (pintype "passive+no_connect"))
    )
    (net (code "95") (name "unconnected-(U15-PB10-PadJ7)") (class "Default")
      (node (ref "U15") (pin "J7") (pinfunction "PB10_J7") (pintype "passive+no_connect"))
    )
    (net (code "96") (name "unconnected-(U15-PB11-PadK7)") (class "Default")
      (node (ref "U15") (pin "K7") (pinfunction "PB11_K7") (pintype "passive+no_connect"))
    )
    (net (code "97") (name "unconnected-(U15-PB12-PadK8)") (class "Default")
      (node (ref "U15") (pin "K8") (pinfunction "PB12_K8") (pintype "passive+no_connect"))
    )
    (net (code "98") (name "unconnected-(U15-PB13-PadJ8)") (class "Default")
      (node (ref "U15") (pin "J8") (pinfunction "PB13_J8") (pintype "passive+no_connect"))
    )
    (net (code "99") (name "unconnected-(U15-PB14-PadH10)") (class "Default")
      (node (ref "U15") (pin "H10") (pinfunction "PB14_H10") (pintype "passive+no_connect"))
    )
    (net (code "100") (name "unconnected-(U15-PB15-PadG10)") (class "Default")
      (node (ref "U15") (pin "G10") (pinfunction "PB15_G10") (pintype "passive+no_connect"))
    )
    (net (code "101") (name "unconnected-(U15-PC3_C-PadF3)") (class "Default")
      (node (ref "U15") (pin "F3") (pinfunction "PC3_C_F3") (pintype "passive+no_connect"))
    )
    (net (code "102") (name "unconnected-(U15-PC11-PadB8)") (class "Default")
      (node (ref "U15") (pin "B8") (pinfunction "PC11_B8") (pintype "passive+no_connect"))
    )
    (net (code "103") (name "unconnected-(U15-PC14-OSC32_IN-PadA1)") (class "Default")
      (node (ref "U15") (pin "A1") (pinfunction "PC14-OSC32_IN_A1") (pintype "passive+no_connect"))
    )
    (net (code "104") (name "unconnected-(U15-PC15-OSC32_OUT-PadB1)") (class "Default")
      (node (ref "U15") (pin "B1") (pinfunction "PC15-OSC32_OUT_B1") (pintype "passive+no_connect"))
    )
    (net (code "105") (name "unconnected-(U15-PD6-PadC6)") (class "Default")
      (node (ref "U15") (pin "C6") (pinfunction "PD6_C6") (pintype "passive+no_connect"))
    )
    (net (code "106") (name "unconnected-(U15-PD7-PadD6)") (class "Default")
      (node (ref "U15") (pin "D6") (pinfunction "PD7_D6") (pintype "passive+no_connect"))
    )
    (net (code "107") (name "unconnected-(U15-PE6-PadE3)") (class "Default")
      (node (ref "U15") (pin "E3") (pinfunction "PE6_E3") (pintype "passive+no_connect"))
    )
    (net (code "108") (name "unconnected-(U15-PE7-PadH5)") (class "Default")
      (node (ref "U15") (pin "H5") (pinfunction "PE7_H5") (pintype "passive+no_connect"))
    )
    (net (code "109") (name "unconnected-(USBC1-SBU1-PadA8)") (class "Default")
      (node (ref "USBC1") (pin "A8") (pinfunction "SBU1_A8") (pintype "passive+no_connect"))
    )
    (net (code "110") (name "unconnected-(USBC1-SBU2-PadB8)") (class "Default")
      (node (ref "USBC1") (pin "B8") (pinfunction "SBU2_B8") (pintype "passive+no_connect"))
    )
    (net (code "111") (name "unconnected-(X1-GND-Pad2)") (class "Default")
      (node (ref "X1") (pin "2") (pinfunction "GND_2") (pintype "passive+no_connect"))
    )
    (net (code "112") (name "unconnected-(X1-GND-Pad4)") (class "Default")
      (node (ref "X1") (pin "4") (pinfunction "GND_4") (pintype "passive+no_connect"))
    )
  )
)
